# PCB-ARD-MXBOS.net
KiCad netlist of a schematic drawn in EAGLE
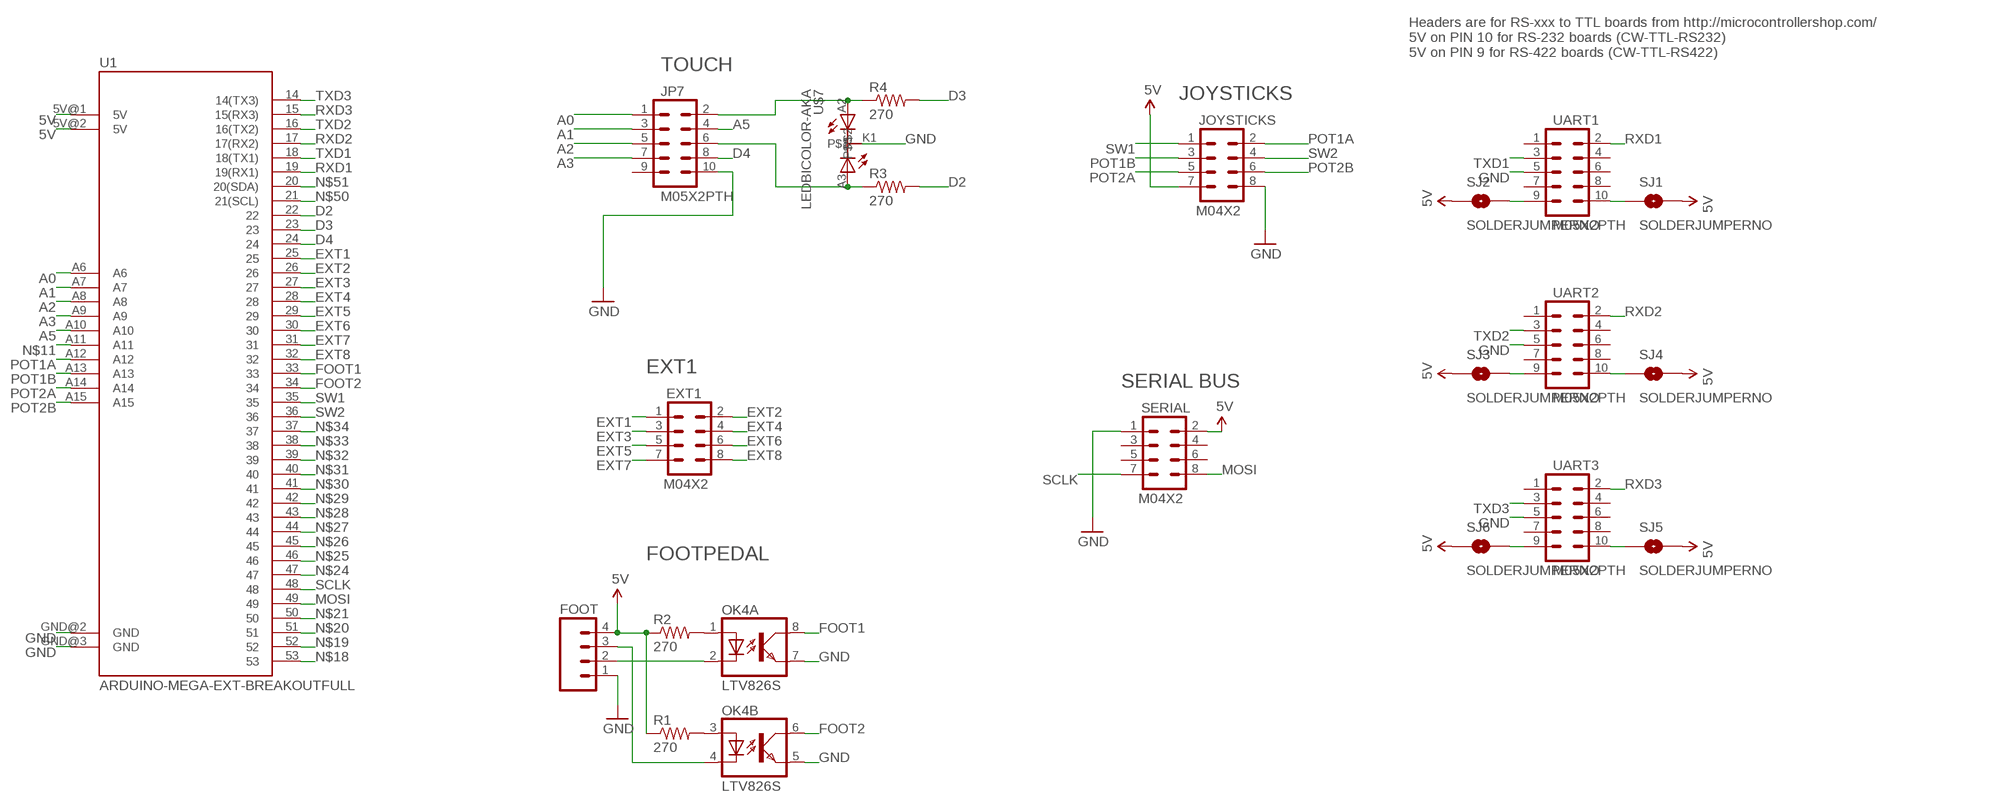
[diagram p0: schematic, sheet 1]

(export (version "E")
  (design (tool "Eeschema 10.0.6"))
  (components
    (comp (ref "EXT1")
      (value "M04X2")
      (footprint "eagle-import:2X4")
      (libsource (lib "eagle-import") (part "M04X2"))
    )
    (comp (ref "FOOT")
      (value "M04LOCK")
      (footprint "eagle-import:1X04_LOCK")
      (libsource (lib "eagle-import") (part "M04LOCK"))
    )
    (comp (ref "JOYSTICKS")
      (value "M04X2")
      (footprint "eagle-import:2X4")
      (libsource (lib "eagle-import") (part "M04X2"))
    )
    (comp (ref "JP7")
      (value "M05X2PTH")
      (footprint "eagle-import:AVR_ICSP")
      (libsource (lib "eagle-import") (part "M05X2PTH"))
    )
    (comp (ref "OK4")
      (value "LTV826S")
      (footprint "eagle-import:DIL8-SMD")
      (libsource (lib "eagle-import") (part "LTV826S"))
    )
    (comp (ref "R1")
      (value "270")
      (footprint "eagle-import:0603-RES")
      (libsource (lib "eagle-import") (part "RESISTOR0603-RES"))
    )
    (comp (ref "R2")
      (value "270")
      (footprint "eagle-import:0603-RES")
      (libsource (lib "eagle-import") (part "RESISTOR0603-RES"))
    )
    (comp (ref "R3")
      (value "270")
      (footprint "eagle-import:0603-RES")
      (libsource (lib "eagle-import") (part "RESISTOR0603-RES"))
    )
    (comp (ref "R4")
      (value "270")
      (footprint "eagle-import:0603-RES")
      (libsource (lib "eagle-import") (part "RESISTOR0603-RES"))
    )
    (comp (ref "SERIAL")
      (value "M04X2")
      (footprint "eagle-import:2X4")
      (libsource (lib "eagle-import") (part "M04X2"))
    )
    (comp (ref "SJ1")
      (value "SOLDERJUMPERNO")
      (footprint "eagle-import:SJ_2S-NO")
      (libsource (lib "eagle-import") (part "SOLDERJUMPERNO"))
    )
    (comp (ref "SJ2")
      (value "SOLDERJUMPERNO")
      (footprint "eagle-import:SJ_2S-NO")
      (libsource (lib "eagle-import") (part "SOLDERJUMPERNO"))
    )
    (comp (ref "SJ3")
      (value "SOLDERJUMPERNO")
      (footprint "eagle-import:SJ_2S-NO")
      (libsource (lib "eagle-import") (part "SOLDERJUMPERNO"))
    )
    (comp (ref "SJ4")
      (value "SOLDERJUMPERNO")
      (footprint "eagle-import:SJ_2S-NO")
      (libsource (lib "eagle-import") (part "SOLDERJUMPERNO"))
    )
    (comp (ref "SJ5")
      (value "SOLDERJUMPERNO")
      (footprint "eagle-import:SJ_2S-NO")
      (libsource (lib "eagle-import") (part "SOLDERJUMPERNO"))
    )
    (comp (ref "SJ6")
      (value "SOLDERJUMPERNO")
      (footprint "eagle-import:SJ_2S-NO")
      (libsource (lib "eagle-import") (part "SOLDERJUMPERNO"))
    )
    (comp (ref "U$7")
      (value "LEDBICOLOR-AKA")
      (footprint "eagle-import:LED5MM-BICOLOR")
      (libsource (lib "eagle-import") (part "LEDBICOLOR-AKA"))
    )
    (comp (ref "U1")
      (value "ARDUINO-MEGA-EXT-BREAKOUTFULL")
      (footprint "eagle-import:ARDUINO_MEGA_EXT_BREAKOUT")
      (libsource (lib "eagle-import") (part "ARDUINO-MEGA-EXT-BREAKOUTFULL"))
    )
    (comp (ref "UART1")
      (value "M05X2PTH")
      (footprint "eagle-import:AVR_ICSP")
      (libsource (lib "eagle-import") (part "M05X2PTH"))
    )
    (comp (ref "UART2")
      (value "M05X2PTH")
      (footprint "eagle-import:AVR_ICSP")
      (libsource (lib "eagle-import") (part "M05X2PTH"))
    )
    (comp (ref "UART3")
      (value "M05X2PTH")
      (footprint "eagle-import:AVR_ICSP")
      (libsource (lib "eagle-import") (part "M05X2PTH"))
    )
  )
  (nets
    (net (code "1") (name "/A0") (class "Default")
      (node (ref "JP7") (pin "1") (pinfunction "1_1") (pintype "passive"))
      (node (ref "U1") (pin "A6") (pinfunction "A6_A6") (pintype "bidirectional"))
    )
    (net (code "2") (name "/A1") (class "Default")
      (node (ref "JP7") (pin "3") (pinfunction "3_3") (pintype "passive"))
      (node (ref "U1") (pin "A7") (pinfunction "A7_A7") (pintype "bidirectional"))
    )
    (net (code "3") (name "/A2") (class "Default")
      (node (ref "JP7") (pin "5") (pinfunction "5_5") (pintype "passive"))
      (node (ref "U1") (pin "A8") (pinfunction "A8_A8") (pintype "bidirectional"))
    )
    (net (code "4") (name "/A3") (class "Default")
      (node (ref "JP7") (pin "7") (pinfunction "7_7") (pintype "passive"))
      (node (ref "U1") (pin "A9") (pinfunction "A9_A9") (pintype "bidirectional"))
    )
    (net (code "5") (name "/A5") (class "Default")
      (node (ref "JP7") (pin "4") (pinfunction "4_4") (pintype "passive"))
      (node (ref "U1") (pin "A10") (pinfunction "A10_A10") (pintype "bidirectional"))
    )
    (net (code "6") (name "/D2") (class "Default")
      (node (ref "R3") (pin "2") (pinfunction "2_2") (pintype "passive"))
      (node (ref "U1") (pin "22") (pinfunction "22_22") (pintype "bidirectional"))
    )
    (net (code "7") (name "/D3") (class "Default")
      (node (ref "R4") (pin "2") (pinfunction "2_2") (pintype "passive"))
      (node (ref "U1") (pin "23") (pinfunction "23_23") (pintype "bidirectional"))
    )
    (net (code "8") (name "/D4") (class "Default")
      (node (ref "JP7") (pin "8") (pinfunction "8_8") (pintype "passive"))
      (node (ref "U1") (pin "24") (pinfunction "24_24") (pintype "bidirectional"))
    )
    (net (code "9") (name "/EXT1") (class "Default")
      (node (ref "EXT1") (pin "1") (pinfunction "1_1") (pintype "passive"))
      (node (ref "U1") (pin "25") (pinfunction "25_25") (pintype "bidirectional"))
    )
    (net (code "10") (name "/EXT2") (class "Default")
      (node (ref "EXT1") (pin "2") (pinfunction "2_2") (pintype "passive"))
      (node (ref "U1") (pin "26") (pinfunction "26_26") (pintype "bidirectional"))
    )
    (net (code "11") (name "/EXT3") (class "Default")
      (node (ref "EXT1") (pin "3") (pinfunction "3_3") (pintype "passive"))
      (node (ref "U1") (pin "27") (pinfunction "27_27") (pintype "bidirectional"))
    )
    (net (code "12") (name "/EXT4") (class "Default")
      (node (ref "EXT1") (pin "4") (pinfunction "4_4") (pintype "passive"))
      (node (ref "U1") (pin "28") (pinfunction "28_28") (pintype "bidirectional"))
    )
    (net (code "13") (name "/EXT5") (class "Default")
      (node (ref "EXT1") (pin "5") (pinfunction "5_5") (pintype "passive"))
      (node (ref "U1") (pin "29") (pinfunction "29_29") (pintype "bidirectional"))
    )
    (net (code "14") (name "/EXT6") (class "Default")
      (node (ref "EXT1") (pin "6") (pinfunction "6_6") (pintype "passive"))
      (node (ref "U1") (pin "30") (pinfunction "30_30") (pintype "bidirectional"))
    )
    (net (code "15") (name "/EXT7") (class "Default")
      (node (ref "EXT1") (pin "7") (pinfunction "7_7") (pintype "passive"))
      (node (ref "U1") (pin "31") (pinfunction "31_31") (pintype "bidirectional"))
    )
    (net (code "16") (name "/EXT8") (class "Default")
      (node (ref "EXT1") (pin "8") (pinfunction "8_8") (pintype "passive"))
      (node (ref "U1") (pin "32") (pinfunction "32_32") (pintype "bidirectional"))
    )
    (net (code "17") (name "/FOOT1") (class "Default")
      (node (ref "OK4") (pin "8") (pinfunction "COL_8") (pintype "passive"))
      (node (ref "U1") (pin "33") (pinfunction "33_33") (pintype "bidirectional"))
    )
    (net (code "18") (name "/FOOT2") (class "Default")
      (node (ref "OK4") (pin "6") (pinfunction "COL_6") (pintype "passive"))
      (node (ref "U1") (pin "34") (pinfunction "34_34") (pintype "bidirectional"))
    )
    (net (code "19") (name "/MOSI") (class "Default")
      (node (ref "SERIAL") (pin "8") (pinfunction "8_8") (pintype "passive"))
      (node (ref "U1") (pin "49") (pinfunction "49_49") (pintype "bidirectional"))
    )
    (net (code "20") (name "/N$11") (class "Default")
      (node (ref "U1") (pin "A11") (pinfunction "A11_A11") (pintype "bidirectional"))
    )
    (net (code "21") (name "/N$18") (class "Default")
      (node (ref "U1") (pin "53") (pinfunction "53_53") (pintype "bidirectional"))
    )
    (net (code "22") (name "/N$19") (class "Default")
      (node (ref "U1") (pin "52") (pinfunction "52_52") (pintype "bidirectional"))
    )
    (net (code "23") (name "/N$20") (class "Default")
      (node (ref "U1") (pin "51") (pinfunction "51_51") (pintype "bidirectional"))
    )
    (net (code "24") (name "/N$21") (class "Default")
      (node (ref "U1") (pin "50") (pinfunction "50_50") (pintype "bidirectional"))
    )
    (net (code "25") (name "/N$24") (class "Default")
      (node (ref "U1") (pin "47") (pinfunction "47_47") (pintype "bidirectional"))
    )
    (net (code "26") (name "/N$25") (class "Default")
      (node (ref "U1") (pin "46") (pinfunction "46_46") (pintype "bidirectional"))
    )
    (net (code "27") (name "/N$26") (class "Default")
      (node (ref "U1") (pin "45") (pinfunction "45_45") (pintype "bidirectional"))
    )
    (net (code "28") (name "/N$27") (class "Default")
      (node (ref "U1") (pin "44") (pinfunction "44_44") (pintype "bidirectional"))
    )
    (net (code "29") (name "/N$28") (class "Default")
      (node (ref "U1") (pin "43") (pinfunction "43_43") (pintype "bidirectional"))
    )
    (net (code "30") (name "/N$29") (class "Default")
      (node (ref "U1") (pin "42") (pinfunction "42_42") (pintype "bidirectional"))
    )
    (net (code "31") (name "/N$30") (class "Default")
      (node (ref "U1") (pin "41") (pinfunction "41_41") (pintype "bidirectional"))
    )
    (net (code "32") (name "/N$31") (class "Default")
      (node (ref "U1") (pin "40") (pinfunction "40_40") (pintype "bidirectional"))
    )
    (net (code "33") (name "/N$32") (class "Default")
      (node (ref "U1") (pin "39") (pinfunction "39_39") (pintype "bidirectional"))
    )
    (net (code "34") (name "/N$33") (class "Default")
      (node (ref "U1") (pin "38") (pinfunction "38_38") (pintype "bidirectional"))
    )
    (net (code "35") (name "/N$34") (class "Default")
      (node (ref "U1") (pin "37") (pinfunction "37_37") (pintype "bidirectional"))
    )
    (net (code "36") (name "/N$50") (class "Default")
      (node (ref "U1") (pin "21") (pinfunction "21(SCL)_21") (pintype "bidirectional"))
    )
    (net (code "37") (name "/N$51") (class "Default")
      (node (ref "U1") (pin "20") (pinfunction "20(SDA)_20") (pintype "bidirectional"))
    )
    (net (code "38") (name "/POT1A") (class "Default")
      (node (ref "JOYSTICKS") (pin "2") (pinfunction "2_2") (pintype "passive"))
      (node (ref "U1") (pin "A12") (pinfunction "A12_A12") (pintype "bidirectional"))
    )
    (net (code "39") (name "/POT1B") (class "Default")
      (node (ref "JOYSTICKS") (pin "3") (pinfunction "3_3") (pintype "passive"))
      (node (ref "U1") (pin "A13") (pinfunction "A13_A13") (pintype "bidirectional"))
    )
    (net (code "40") (name "/POT2A") (class "Default")
      (node (ref "JOYSTICKS") (pin "5") (pinfunction "5_5") (pintype "passive"))
      (node (ref "U1") (pin "A14") (pinfunction "A14_A14") (pintype "bidirectional"))
    )
    (net (code "41") (name "/POT2B") (class "Default")
      (node (ref "JOYSTICKS") (pin "6") (pinfunction "6_6") (pintype "passive"))
      (node (ref "U1") (pin "A15") (pinfunction "A15_A15") (pintype "bidirectional"))
    )
    (net (code "42") (name "/RXD1") (class "Default")
      (node (ref "U1") (pin "19") (pinfunction "19(RX1)_19") (pintype "bidirectional"))
      (node (ref "UART1") (pin "2") (pinfunction "2_2") (pintype "passive"))
    )
    (net (code "43") (name "/RXD2") (class "Default")
      (node (ref "U1") (pin "17") (pinfunction "17(RX2)_17") (pintype "bidirectional"))
      (node (ref "UART2") (pin "2") (pinfunction "2_2") (pintype "passive"))
    )
    (net (code "44") (name "/RXD3") (class "Default")
      (node (ref "U1") (pin "15") (pinfunction "15(RX3)_15") (pintype "bidirectional"))
      (node (ref "UART3") (pin "2") (pinfunction "2_2") (pintype "passive"))
    )
    (net (code "45") (name "/SCLK") (class "Default")
      (node (ref "SERIAL") (pin "7") (pinfunction "7_7") (pintype "passive"))
      (node (ref "U1") (pin "48") (pinfunction "48_48") (pintype "bidirectional"))
    )
    (net (code "46") (name "/SW1") (class "Default")
      (node (ref "JOYSTICKS") (pin "1") (pinfunction "1_1") (pintype "passive"))
      (node (ref "U1") (pin "35") (pinfunction "35_35") (pintype "bidirectional"))
    )
    (net (code "47") (name "/SW2") (class "Default")
      (node (ref "JOYSTICKS") (pin "4") (pinfunction "4_4") (pintype "passive"))
      (node (ref "U1") (pin "36") (pinfunction "36_36") (pintype "bidirectional"))
    )
    (net (code "48") (name "/TXD1") (class "Default")
      (node (ref "U1") (pin "18") (pinfunction "18(TX1)_18") (pintype "bidirectional"))
      (node (ref "UART1") (pin "3") (pinfunction "3_3") (pintype "passive"))
    )
    (net (code "49") (name "/TXD2") (class "Default")
      (node (ref "U1") (pin "16") (pinfunction "16(TX2)_16") (pintype "bidirectional"))
      (node (ref "UART2") (pin "3") (pinfunction "3_3") (pintype "passive"))
    )
    (net (code "50") (name "/TXD3") (class "Default")
      (node (ref "U1") (pin "14") (pinfunction "14(TX3)_14") (pintype "bidirectional"))
      (node (ref "UART3") (pin "3") (pinfunction "3_3") (pintype "passive"))
    )
    (net (code "51") (name "5V") (class "Default")
      (node (ref "FOOT") (pin "4") (pinfunction "4_4") (pintype "passive"))
      (node (ref "JOYSTICKS") (pin "7") (pinfunction "7_7") (pintype "passive"))
      (node (ref "R1") (pin "1") (pinfunction "1_1") (pintype "passive"))
      (node (ref "R2") (pin "1") (pinfunction "1_1") (pintype "passive"))
      (node (ref "SERIAL") (pin "2") (pinfunction "2_2") (pintype "passive"))
      (node (ref "SJ1") (pin "2") (pinfunction "2_2") (pintype "passive"))
      (node (ref "SJ2") (pin "1") (pinfunction "1_1") (pintype "passive"))
      (node (ref "SJ3") (pin "1") (pinfunction "1_1") (pintype "passive"))
      (node (ref "SJ4") (pin "2") (pinfunction "2_2") (pintype "passive"))
      (node (ref "SJ5") (pin "2") (pinfunction "2_2") (pintype "passive"))
      (node (ref "SJ6") (pin "1") (pinfunction "1_1") (pintype "passive"))
      (node (ref "U1") (pin "5V@1") (pinfunction "5V_5V@1") (pintype "bidirectional"))
      (node (ref "U1") (pin "5V@2") (pinfunction "5V_5V@2") (pintype "bidirectional"))
    )
    (net (code "52") (name "GND") (class "Default")
      (node (ref "FOOT") (pin "1") (pinfunction "1_1") (pintype "passive"))
      (node (ref "JOYSTICKS") (pin "8") (pinfunction "8_8") (pintype "passive"))
      (node (ref "JP7") (pin "10") (pinfunction "10_10") (pintype "passive"))
      (node (ref "OK4") (pin "5") (pinfunction "EMIT_5") (pintype "passive"))
      (node (ref "OK4") (pin "7") (pinfunction "EMIT_7") (pintype "passive"))
      (node (ref "SERIAL") (pin "1") (pinfunction "1_1") (pintype "passive"))
      (node (ref "U$7") (pin "K1") (pinfunction "P$1_K1") (pintype "bidirectional"))
      (node (ref "U1") (pin "GND@2") (pinfunction "GND_GND@2") (pintype "bidirectional"))
      (node (ref "U1") (pin "GND@3") (pinfunction "GND_GND@3") (pintype "bidirectional"))
      (node (ref "UART1") (pin "5") (pinfunction "5_5") (pintype "passive"))
      (node (ref "UART2") (pin "5") (pinfunction "5_5") (pintype "passive"))
      (node (ref "UART3") (pin "5") (pinfunction "5_5") (pintype "passive"))
    )
    (net (code "53") (name "Net-(OK4A-A)") (class "Default")
      (node (ref "OK4") (pin "1") (pinfunction "A_1") (pintype "passive"))
      (node (ref "R2") (pin "2") (pinfunction "2_2") (pintype "passive"))
    )
    (net (code "54") (name "Net-(OK4A-C)") (class "Default")
      (node (ref "FOOT") (pin "2") (pinfunction "2_2") (pintype "passive"))
      (node (ref "OK4") (pin "2") (pinfunction "C_2") (pintype "passive"))
    )
    (net (code "55") (name "Net-(OK4B-A)") (class "Default")
      (node (ref "OK4") (pin "3") (pinfunction "A_3") (pintype "passive"))
      (node (ref "R1") (pin "2") (pinfunction "2_2") (pintype "passive"))
    )
    (net (code "56") (name "Net-(OK4B-C)") (class "Default")
      (node (ref "FOOT") (pin "3") (pinfunction "3_3") (pintype "passive"))
      (node (ref "OK4") (pin "4") (pinfunction "C_4") (pintype "passive"))
    )
    (net (code "57") (name "Net-(SJ1-Pad1)") (class "Default")
      (node (ref "SJ1") (pin "1") (pinfunction "1_1") (pintype "passive"))
      (node (ref "UART1") (pin "10") (pinfunction "10_10") (pintype "passive"))
    )
    (net (code "58") (name "Net-(SJ2-Pad2)") (class "Default")
      (node (ref "SJ2") (pin "2") (pinfunction "2_2") (pintype "passive"))
      (node (ref "UART1") (pin "9") (pinfunction "9_9") (pintype "passive"))
    )
    (net (code "59") (name "Net-(SJ3-Pad2)") (class "Default")
      (node (ref "SJ3") (pin "2") (pinfunction "2_2") (pintype "passive"))
      (node (ref "UART2") (pin "9") (pinfunction "9_9") (pintype "passive"))
    )
    (net (code "60") (name "Net-(SJ4-Pad1)") (class "Default")
      (node (ref "SJ4") (pin "1") (pinfunction "1_1") (pintype "passive"))
      (node (ref "UART2") (pin "10") (pinfunction "10_10") (pintype "passive"))
    )
    (net (code "61") (name "Net-(SJ5-Pad1)") (class "Default")
      (node (ref "SJ5") (pin "1") (pinfunction "1_1") (pintype "passive"))
      (node (ref "UART3") (pin "10") (pinfunction "10_10") (pintype "passive"))
    )
    (net (code "62") (name "Net-(SJ6-Pad2)") (class "Default")
      (node (ref "SJ6") (pin "2") (pinfunction "2_2") (pintype "passive"))
      (node (ref "UART3") (pin "9") (pinfunction "9_9") (pintype "passive"))
    )
    (net (code "63") (name "Net-(U$7-P$2)") (class "Default")
      (node (ref "JP7") (pin "2") (pinfunction "2_2") (pintype "passive"))
      (node (ref "R4") (pin "1") (pinfunction "1_1") (pintype "passive"))
      (node (ref "U$7") (pin "A2") (pinfunction "P$2_A2") (pintype "bidirectional"))
    )
    (net (code "64") (name "Net-(U$7-P$3)") (class "Default")
      (node (ref "JP7") (pin "6") (pinfunction "6_6") (pintype "passive"))
      (node (ref "R3") (pin "1") (pinfunction "1_1") (pintype "passive"))
      (node (ref "U$7") (pin "A3") (pinfunction "P$3_A3") (pintype "bidirectional"))
    )
    (net (code "65") (name "unconnected-(JP7-Pad9)") (class "Default")
      (node (ref "JP7") (pin "9") (pinfunction "9_9") (pintype "passive"))
    )
    (net (code "66") (name "unconnected-(SERIAL-Pad3)") (class "Default")
      (node (ref "SERIAL") (pin "3") (pinfunction "3_3") (pintype "passive"))
    )
    (net (code "67") (name "unconnected-(SERIAL-Pad4)") (class "Default")
      (node (ref "SERIAL") (pin "4") (pinfunction "4_4") (pintype "passive"))
    )
    (net (code "68") (name "unconnected-(SERIAL-Pad5)") (class "Default")
      (node (ref "SERIAL") (pin "5") (pinfunction "5_5") (pintype "passive"))
    )
    (net (code "69") (name "unconnected-(SERIAL-Pad6)") (class "Default")
      (node (ref "SERIAL") (pin "6") (pinfunction "6_6") (pintype "passive"))
    )
    (net (code "70") (name "unconnected-(UART1-Pad1)") (class "Default")
      (node (ref "UART1") (pin "1") (pinfunction "1_1") (pintype "passive"))
    )
    (net (code "71") (name "unconnected-(UART1-Pad4)") (class "Default")
      (node (ref "UART1") (pin "4") (pinfunction "4_4") (pintype "passive"))
    )
    (net (code "72") (name "unconnected-(UART1-Pad6)") (class "Default")
      (node (ref "UART1") (pin "6") (pinfunction "6_6") (pintype "passive"))
    )
    (net (code "73") (name "unconnected-(UART1-Pad7)") (class "Default")
      (node (ref "UART1") (pin "7") (pinfunction "7_7") (pintype "passive"))
    )
    (net (code "74") (name "unconnected-(UART1-Pad8)") (class "Default")
      (node (ref "UART1") (pin "8") (pinfunction "8_8") (pintype "passive"))
    )
    (net (code "75") (name "unconnected-(UART2-Pad1)") (class "Default")
      (node (ref "UART2") (pin "1") (pinfunction "1_1") (pintype "passive"))
    )
    (net (code "76") (name "unconnected-(UART2-Pad4)") (class "Default")
      (node (ref "UART2") (pin "4") (pinfunction "4_4") (pintype "passive"))
    )
    (net (code "77") (name "unconnected-(UART2-Pad6)") (class "Default")
      (node (ref "UART2") (pin "6") (pinfunction "6_6") (pintype "passive"))
    )
    (net (code "78") (name "unconnected-(UART2-Pad7)") (class "Default")
      (node (ref "UART2") (pin "7") (pinfunction "7_7") (pintype "passive"))
    )
    (net (code "79") (name "unconnected-(UART2-Pad8)") (class "Default")
      (node (ref "UART2") (pin "8") (pinfunction "8_8") (pintype "passive"))
    )
    (net (code "80") (name "unconnected-(UART3-Pad1)") (class "Default")
      (node (ref "UART3") (pin "1") (pinfunction "1_1") (pintype "passive"))
    )
    (net (code "81") (name "unconnected-(UART3-Pad4)") (class "Default")
      (node (ref "UART3") (pin "4") (pinfunction "4_4") (pintype "passive"))
    )
    (net (code "82") (name "unconnected-(UART3-Pad6)") (class "Default")
      (node (ref "UART3") (pin "6") (pinfunction "6_6") (pintype "passive"))
    )
    (net (code "83") (name "unconnected-(UART3-Pad7)") (class "Default")
      (node (ref "UART3") (pin "7") (pinfunction "7_7") (pintype "passive"))
    )
    (net (code "84") (name "unconnected-(UART3-Pad8)") (class "Default")
      (node (ref "UART3") (pin "8") (pinfunction "8_8") (pintype "passive"))
    )
  )
)
